# BYH_USB.net
KiCad netlist of a schematic drawn in EasyEDA Pro
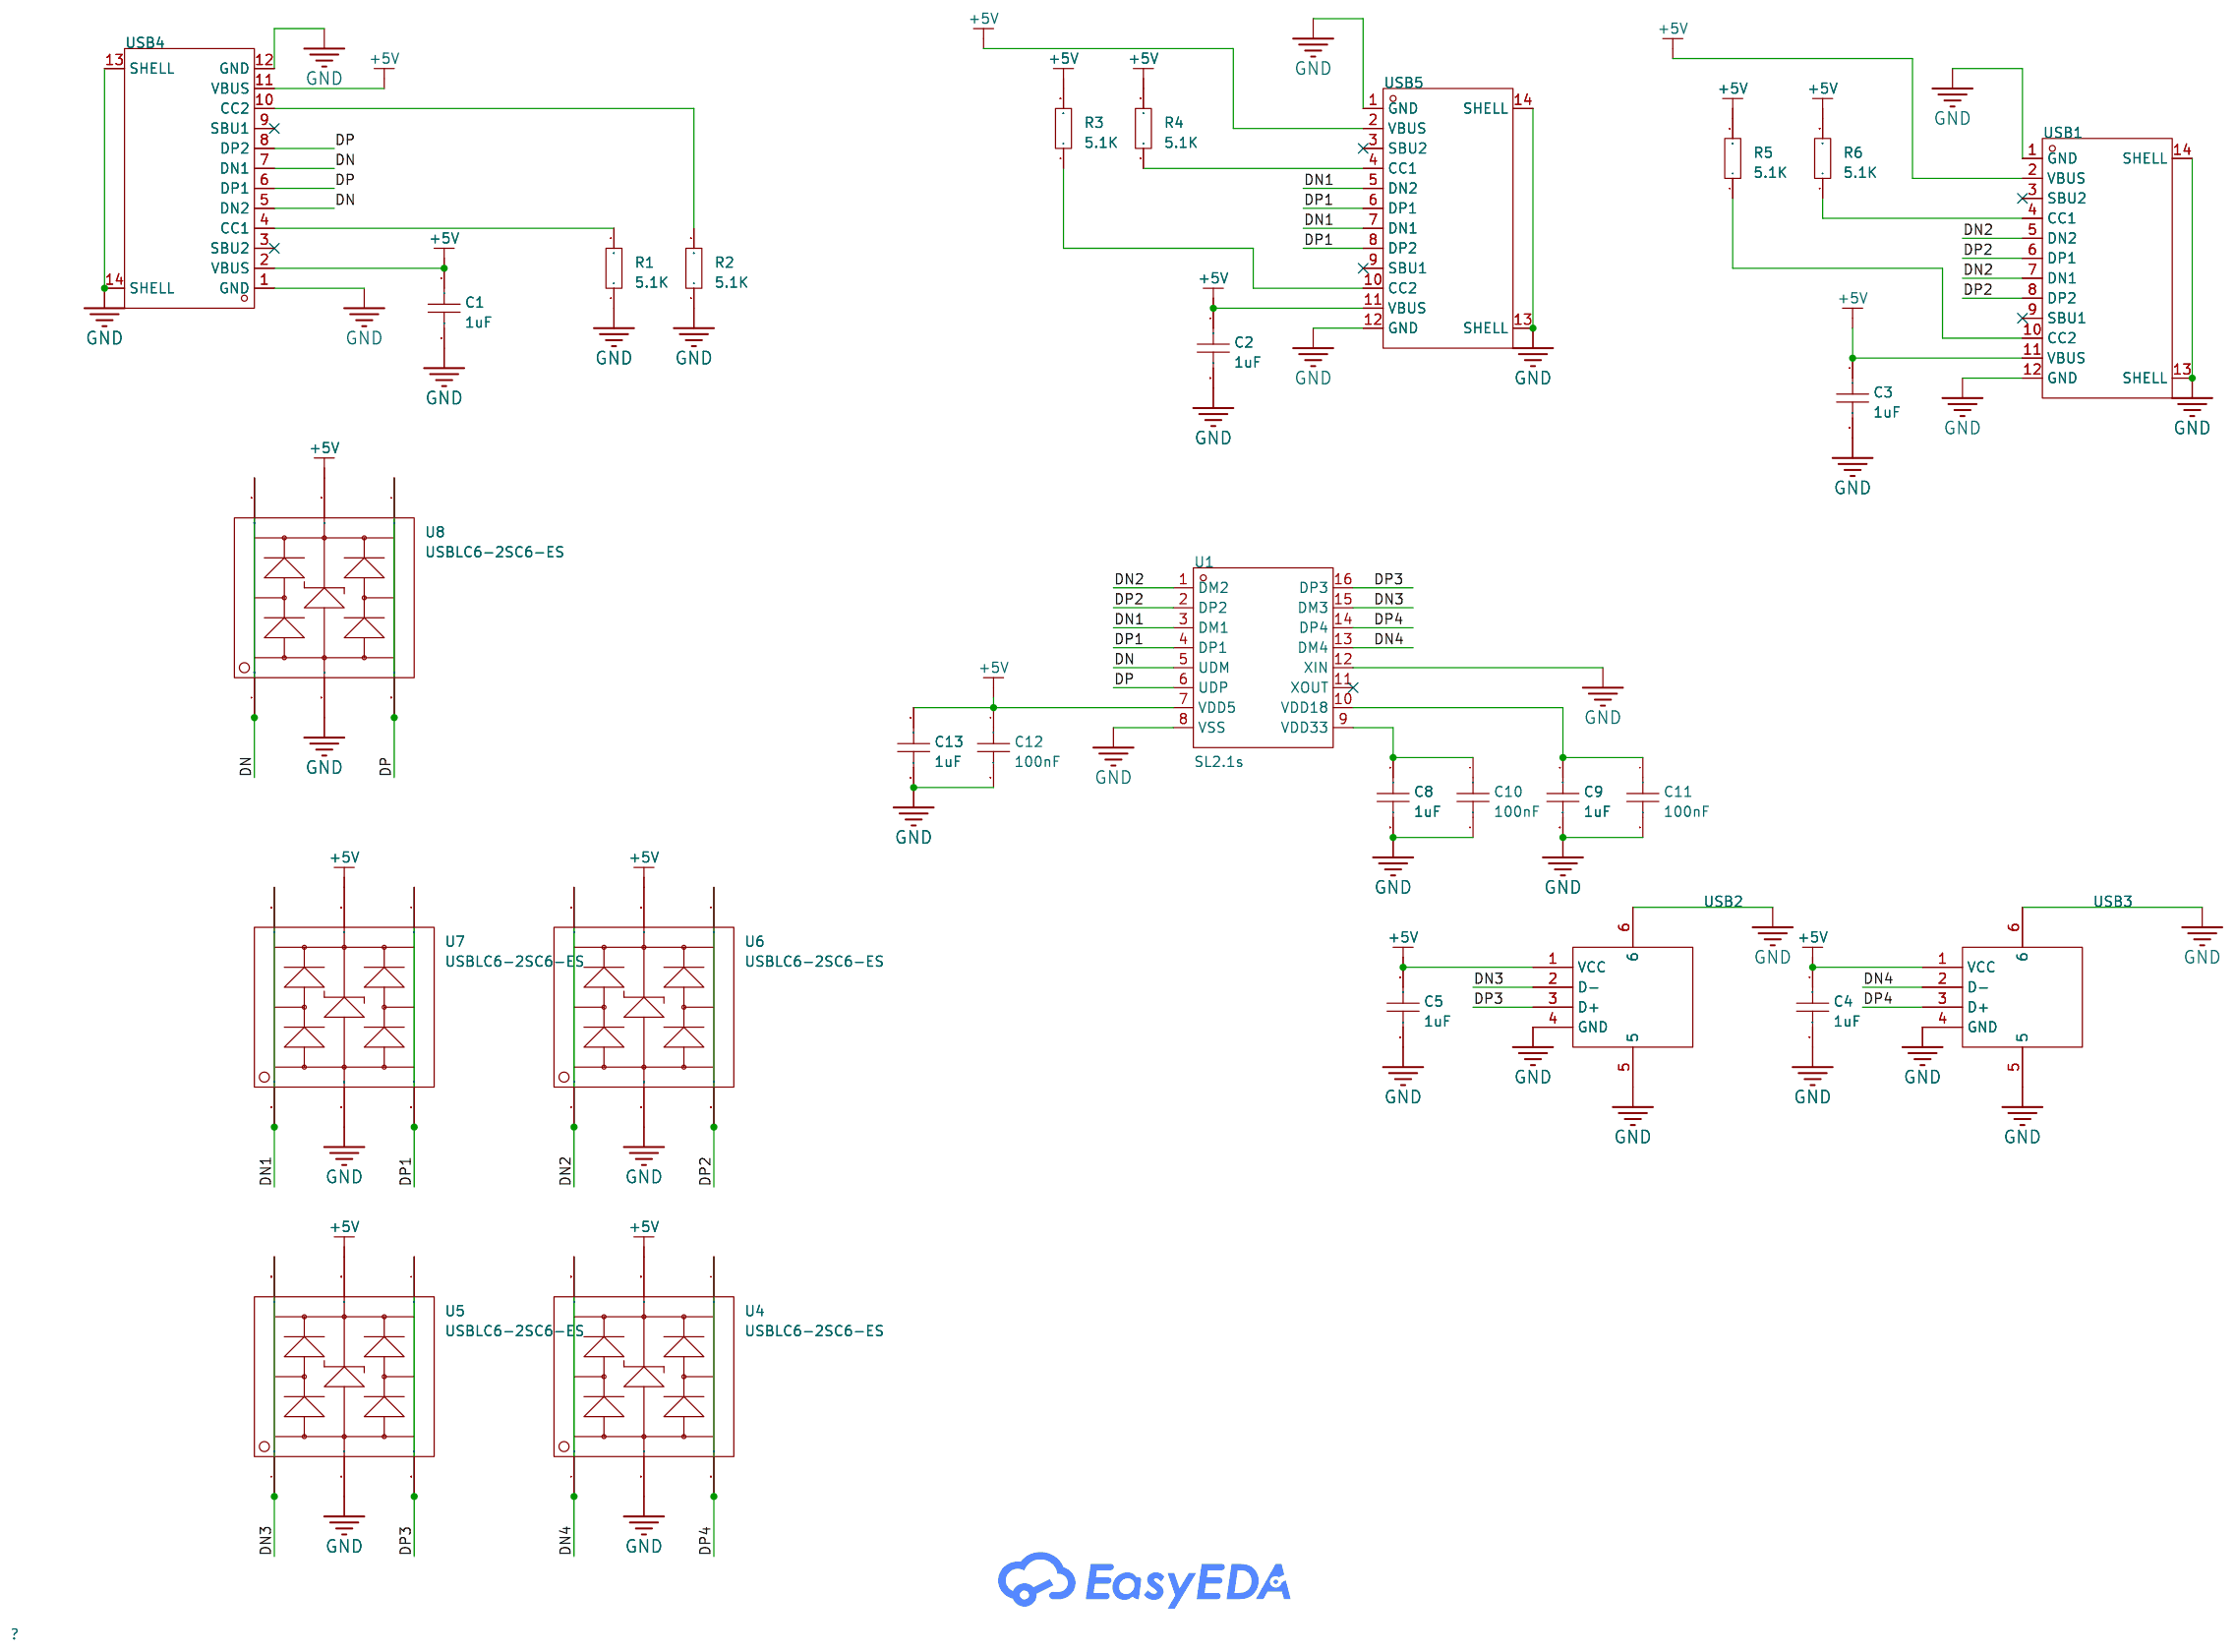
[diagram p0: schematic sheet]

(export (version "E")
  (design (tool "Eeschema 10.0.6"))
  (components
    (comp (ref "C1") (value "1uF") (footprint "easyedapro:C0603") (libsource (lib "easyedapro") (part "CAP")))
    (comp (ref "C2") (value "1uF") (footprint "easyedapro:C0603") (libsource (lib "easyedapro") (part "CAP")))
    (comp (ref "C3") (value "1uF") (footprint "easyedapro:C0603") (libsource (lib "easyedapro") (part "CAP")))
    (comp (ref "C4") (value "1uF") (footprint "easyedapro:C0603") (libsource (lib "easyedapro") (part "CAP")))
    (comp (ref "C5") (value "1uF") (footprint "easyedapro:C0603") (libsource (lib "easyedapro") (part "CAP")))
    (comp (ref "C8") (value "1uF") (footprint "easyedapro:C0603") (libsource (lib "easyedapro") (part "CAP")))
    (comp (ref "C9") (value "1uF") (footprint "easyedapro:C0603") (libsource (lib "easyedapro") (part "CAP")))
    (comp (ref "C10")
      (value "100nF")
      (footprint "easyedapro:C0603")
      (libsource (lib "easyedapro") (part "CAP"))
    )
    (comp (ref "C11")
      (value "100nF")
      (footprint "easyedapro:C0603")
      (libsource (lib "easyedapro") (part "CAP"))
    )
    (comp (ref "C12")
      (value "100nF")
      (footprint "easyedapro:C0603")
      (libsource (lib "easyedapro") (part "CAP"))
    )
    (comp (ref "C13")
      (value "1uF")
      (footprint "easyedapro:C0603")
      (libsource (lib "easyedapro") (part "CAP"))
    )
    (comp (ref "R1")
      (value "5.1K")
      (footprint "easyedapro:R0603")
      (libsource (lib "easyedapro") (part "Res"))
    )
    (comp (ref "R2")
      (value "5.1K")
      (footprint "easyedapro:R0603")
      (libsource (lib "easyedapro") (part "Res"))
    )
    (comp (ref "R3")
      (value "5.1K")
      (footprint "easyedapro:R0603")
      (libsource (lib "easyedapro") (part "Res"))
    )
    (comp (ref "R4")
      (value "5.1K")
      (footprint "easyedapro:R0603")
      (libsource (lib "easyedapro") (part "Res"))
    )
    (comp (ref "R5")
      (value "5.1K")
      (footprint "easyedapro:R0603")
      (libsource (lib "easyedapro") (part "Res"))
    )
    (comp (ref "R6")
      (value "5.1K")
      (footprint "easyedapro:R0603")
      (libsource (lib "easyedapro") (part "Res"))
    )
    (comp (ref "U1")
      (value "SL2.1s")
      (footprint "easyedapro:SSOP-16_L4.6-W2.6-P0.53-LS4.0-BL")
      (fields (field (name "Manufacturer") "CoreChips(和芯润德)"))
      (libsource (lib "easyedapro") (part "SL2.1S"))
    )
    (comp (ref "U4")
      (value "USBLC6-2SC6-ES")
      (footprint "easyedapro:SOT-23-6_L2.9-W1.6-P0.95-LS2.8-BR")
      (fields (field (name "Manufacturer") "ElecSuper(静芯)"))
      (libsource (lib "easyedapro") (part "USBLC6-2SC6-ES"))
    )
    (comp (ref "U5")
      (value "USBLC6-2SC6-ES")
      (footprint "easyedapro:SOT-23-6_L2.9-W1.6-P0.95-LS2.8-BR")
      (fields (field (name "Manufacturer") "ElecSuper(静芯)"))
      (libsource (lib "easyedapro") (part "USBLC6-2SC6-ES"))
    )
    (comp (ref "U6")
      (value "USBLC6-2SC6-ES")
      (footprint "easyedapro:SOT-23-6_L2.9-W1.6-P0.95-LS2.8-BR")
      (fields (field (name "Manufacturer") "ElecSuper(静芯)"))
      (libsource (lib "easyedapro") (part "USBLC6-2SC6-ES"))
    )
    (comp (ref "U7")
      (value "USBLC6-2SC6-ES")
      (footprint "easyedapro:SOT-23-6_L2.9-W1.6-P0.95-LS2.8-BR")
      (fields (field (name "Manufacturer") "ElecSuper(静芯)"))
      (libsource (lib "easyedapro") (part "USBLC6-2SC6-ES"))
    )
    (comp (ref "U8")
      (value "USBLC6-2SC6-ES")
      (footprint "easyedapro:SOT-23-6_L2.9-W1.6-P0.95-LS2.8-BR")
      (fields (field (name "Manufacturer") "ElecSuper(静芯)"))
      (libsource (lib "easyedapro") (part "USBLC6-2SC6-ES"))
    )
    (comp (ref "USB1")
      (value "TYPE-C 16PIN 2MD(073)")
      (footprint "easyedapro:USB-C-SMD_TYPE-C-6PIN-2MD-073")
      (fields (field (name "Manufacturer") "SHOU HAN(首韩)"))
      (libsource (lib "easyedapro") (part "TYPE-C 16PIN 2MD(073)"))
    )
    (comp (ref "USB2")
      (value "10.0 QHHTZB6.3")
      (footprint "easyedapro:USB-A-TH_10.0QHHTZB6.3")
      (fields (field (name "Manufacturer") "SHOU HAN(首韩)"))
      (libsource (lib "easyedapro") (part "10.0 QHHTZB6.3"))
    )
    (comp (ref "USB3")
      (value "10.0 QHHTZB6.3")
      (footprint "easyedapro:USB-A-TH_10.0QHHTZB6.3")
      (fields (field (name "Manufacturer") "SHOU HAN(首韩)"))
      (libsource (lib "easyedapro") (part "10.0 QHHTZB6.3"))
    )
    (comp (ref "USB4")
      (value "TYPE-C 16PIN 2MD(073)")
      (footprint "easyedapro:USB-C-SMD_TYPE-C-6PIN-2MD-073")
      (fields (field (name "Manufacturer") "SHOU HAN(首韩)"))
      (libsource (lib "easyedapro") (part "TYPE-C 16PIN 2MD(073)"))
    )
    (comp (ref "USB5")
      (value "TYPE-C 16PIN 2MD(073)")
      (footprint "easyedapro:USB-C-SMD_TYPE-C-6PIN-2MD-073")
      (fields (field (name "Manufacturer") "SHOU HAN(首韩)"))
      (libsource (lib "easyedapro") (part "TYPE-C 16PIN 2MD(073)"))
    )
  )
  (nets
    (net (code "1") (name "+5V") (class "Default")
      (node (ref "C1") (pin "1") (pinfunction "1_1") (pintype "input"))
      (node (ref "C12") (pin "1") (pinfunction "1_1") (pintype "input"))
      (node (ref "C13") (pin "1") (pinfunction "1_1") (pintype "input"))
      (node (ref "C2") (pin "1") (pinfunction "1_1") (pintype "input"))
      (node (ref "C3") (pin "1") (pinfunction "1_1") (pintype "input"))
      (node (ref "C4") (pin "1") (pinfunction "1_1") (pintype "input"))
      (node (ref "C5") (pin "1") (pinfunction "1_1") (pintype "input"))
      (node (ref "R3") (pin "2") (pinfunction "2_2") (pintype "input"))
      (node (ref "R4") (pin "2") (pinfunction "2_2") (pintype "input"))
      (node (ref "R5") (pin "2") (pinfunction "2_2") (pintype "input"))
      (node (ref "R6") (pin "2") (pinfunction "2_2") (pintype "input"))
      (node (ref "U1") (pin "7") (pinfunction "VDD5_7") (pintype "unspecified"))
      (node (ref "U4") (pin "5") (pinfunction "VCC_5") (pintype "input"))
      (node (ref "U5") (pin "5") (pinfunction "VCC_5") (pintype "input"))
      (node (ref "U6") (pin "5") (pinfunction "VCC_5") (pintype "input"))
      (node (ref "U7") (pin "5") (pinfunction "VCC_5") (pintype "input"))
      (node (ref "U8") (pin "5") (pinfunction "VCC_5") (pintype "input"))
      (node (ref "USB1") (pin "11") (pinfunction "VBUS_11") (pintype "unspecified"))
      (node (ref "USB1") (pin "2") (pinfunction "VBUS_2") (pintype "unspecified"))
      (node (ref "USB2") (pin "1") (pinfunction "VCC_1") (pintype "unspecified"))
      (node (ref "USB3") (pin "1") (pinfunction "VCC_1") (pintype "unspecified"))
      (node (ref "USB4") (pin "11") (pinfunction "VBUS_11") (pintype "unspecified"))
      (node (ref "USB4") (pin "2") (pinfunction "VBUS_2") (pintype "unspecified"))
      (node (ref "USB5") (pin "11") (pinfunction "VBUS_11") (pintype "unspecified"))
      (node (ref "USB5") (pin "2") (pinfunction "VBUS_2") (pintype "unspecified"))
    )
    (net (code "2") (name "/DN") (class "Default")
      (node (ref "U1") (pin "5") (pinfunction "UDM_5") (pintype "unspecified"))
      (node (ref "U8") (pin "1") (pinfunction "I/O1_1") (pintype "input"))
      (node (ref "U8") (pin "6") (pinfunction "I/O1_6") (pintype "input"))
      (node (ref "USB4") (pin "5") (pinfunction "DN2_5") (pintype "unspecified"))
      (node (ref "USB4") (pin "7") (pinfunction "DN1_7") (pintype "unspecified"))
    )
    (net (code "3") (name "/DN1") (class "Default")
      (node (ref "U1") (pin "3") (pinfunction "DM1_3") (pintype "unspecified"))
      (node (ref "U7") (pin "1") (pinfunction "I/O1_1") (pintype "input"))
      (node (ref "U7") (pin "6") (pinfunction "I/O1_6") (pintype "input"))
      (node (ref "USB5") (pin "5") (pinfunction "DN2_5") (pintype "unspecified"))
      (node (ref "USB5") (pin "7") (pinfunction "DN1_7") (pintype "unspecified"))
    )
    (net (code "4") (name "/DN2") (class "Default")
      (node (ref "U1") (pin "1") (pinfunction "DM2_1") (pintype "unspecified"))
      (node (ref "U6") (pin "1") (pinfunction "I/O1_1") (pintype "input"))
      (node (ref "U6") (pin "6") (pinfunction "I/O1_6") (pintype "input"))
      (node (ref "USB1") (pin "5") (pinfunction "DN2_5") (pintype "unspecified"))
      (node (ref "USB1") (pin "7") (pinfunction "DN1_7") (pintype "unspecified"))
    )
    (net (code "5") (name "/DN3") (class "Default")
      (node (ref "U1") (pin "15") (pinfunction "DM3_15") (pintype "unspecified"))
      (node (ref "U5") (pin "1") (pinfunction "I/O1_1") (pintype "input"))
      (node (ref "U5") (pin "6") (pinfunction "I/O1_6") (pintype "input"))
      (node (ref "USB2") (pin "2") (pinfunction "D-_2") (pintype "unspecified"))
    )
    (net (code "6") (name "/DN4") (class "Default")
      (node (ref "U1") (pin "13") (pinfunction "DM4_13") (pintype "unspecified"))
      (node (ref "U4") (pin "1") (pinfunction "I/O1_1") (pintype "input"))
      (node (ref "U4") (pin "6") (pinfunction "I/O1_6") (pintype "input"))
      (node (ref "USB3") (pin "2") (pinfunction "D-_2") (pintype "unspecified"))
    )
    (net (code "7") (name "/DP") (class "Default")
      (node (ref "U1") (pin "6") (pinfunction "UDP_6") (pintype "unspecified"))
      (node (ref "U8") (pin "3") (pinfunction "I/O2_3") (pintype "input"))
      (node (ref "U8") (pin "4") (pinfunction "I/O2_4") (pintype "input"))
      (node (ref "USB4") (pin "6") (pinfunction "DP1_6") (pintype "unspecified"))
      (node (ref "USB4") (pin "8") (pinfunction "DP2_8") (pintype "unspecified"))
    )
    (net (code "8") (name "/DP1") (class "Default")
      (node (ref "U1") (pin "4") (pinfunction "DP1_4") (pintype "unspecified"))
      (node (ref "U7") (pin "3") (pinfunction "I/O2_3") (pintype "input"))
      (node (ref "U7") (pin "4") (pinfunction "I/O2_4") (pintype "input"))
      (node (ref "USB5") (pin "6") (pinfunction "DP1_6") (pintype "unspecified"))
      (node (ref "USB5") (pin "8") (pinfunction "DP2_8") (pintype "unspecified"))
    )
    (net (code "9") (name "/DP2") (class "Default")
      (node (ref "U1") (pin "2") (pinfunction "DP2_2") (pintype "unspecified"))
      (node (ref "U6") (pin "3") (pinfunction "I/O2_3") (pintype "input"))
      (node (ref "U6") (pin "4") (pinfunction "I/O2_4") (pintype "input"))
      (node (ref "USB1") (pin "6") (pinfunction "DP1_6") (pintype "unspecified"))
      (node (ref "USB1") (pin "8") (pinfunction "DP2_8") (pintype "unspecified"))
    )
    (net (code "10") (name "/DP3") (class "Default")
      (node (ref "U1") (pin "16") (pinfunction "DP3_16") (pintype "unspecified"))
      (node (ref "U5") (pin "3") (pinfunction "I/O2_3") (pintype "input"))
      (node (ref "U5") (pin "4") (pinfunction "I/O2_4") (pintype "input"))
      (node (ref "USB2") (pin "3") (pinfunction "D+_3") (pintype "unspecified"))
    )
    (net (code "11") (name "/DP4") (class "Default")
      (node (ref "U1") (pin "14") (pinfunction "DP4_14") (pintype "unspecified"))
      (node (ref "U4") (pin "3") (pinfunction "I/O2_3") (pintype "input"))
      (node (ref "U4") (pin "4") (pinfunction "I/O2_4") (pintype "input"))
      (node (ref "USB3") (pin "3") (pinfunction "D+_3") (pintype "unspecified"))
    )
    (net (code "12") (name "GND") (class "Default")
      (node (ref "C1") (pin "2") (pinfunction "2_2") (pintype "input"))
      (node (ref "C10") (pin "2") (pinfunction "2_2") (pintype "input"))
      (node (ref "C11") (pin "2") (pinfunction "2_2") (pintype "input"))
      (node (ref "C12") (pin "2") (pinfunction "2_2") (pintype "input"))
      (node (ref "C13") (pin "2") (pinfunction "2_2") (pintype "input"))
      (node (ref "C2") (pin "2") (pinfunction "2_2") (pintype "input"))
      (node (ref "C3") (pin "2") (pinfunction "2_2") (pintype "input"))
      (node (ref "C4") (pin "2") (pinfunction "2_2") (pintype "input"))
      (node (ref "C5") (pin "2") (pinfunction "2_2") (pintype "input"))
      (node (ref "C8") (pin "2") (pinfunction "2_2") (pintype "input"))
      (node (ref "C9") (pin "2") (pinfunction "2_2") (pintype "input"))
      (node (ref "R1") (pin "1") (pinfunction "1_1") (pintype "input"))
      (node (ref "R2") (pin "1") (pinfunction "1_1") (pintype "input"))
      (node (ref "U1") (pin "12") (pinfunction "XIN_12") (pintype "unspecified"))
      (node (ref "U1") (pin "8") (pinfunction "VSS_8") (pintype "unspecified"))
      (node (ref "U4") (pin "2") (pinfunction "GND_2") (pintype "input"))
      (node (ref "U5") (pin "2") (pinfunction "GND_2") (pintype "input"))
      (node (ref "U6") (pin "2") (pinfunction "GND_2") (pintype "input"))
      (node (ref "U7") (pin "2") (pinfunction "GND_2") (pintype "input"))
      (node (ref "U8") (pin "2") (pinfunction "GND_2") (pintype "input"))
      (node (ref "USB1") (pin "1") (pinfunction "GND_1") (pintype "unspecified"))
      (node (ref "USB1") (pin "12") (pinfunction "GND_12") (pintype "unspecified"))
      (node (ref "USB1") (pin "13") (pinfunction "SHELL_13") (pintype "unspecified"))
      (node (ref "USB1") (pin "14") (pinfunction "SHELL_14") (pintype "unspecified"))
      (node (ref "USB2") (pin "4") (pinfunction "GND_4") (pintype "unspecified"))
      (node (ref "USB2") (pin "5") (pinfunction "5_5") (pintype "unspecified"))
      (node (ref "USB2") (pin "6") (pinfunction "6_6") (pintype "unspecified"))
      (node (ref "USB3") (pin "4") (pinfunction "GND_4") (pintype "unspecified"))
      (node (ref "USB3") (pin "5") (pinfunction "5_5") (pintype "unspecified"))
      (node (ref "USB3") (pin "6") (pinfunction "6_6") (pintype "unspecified"))
      (node (ref "USB4") (pin "1") (pinfunction "GND_1") (pintype "unspecified"))
      (node (ref "USB4") (pin "12") (pinfunction "GND_12") (pintype "unspecified"))
      (node (ref "USB4") (pin "13") (pinfunction "SHELL_13") (pintype "unspecified"))
      (node (ref "USB4") (pin "14") (pinfunction "SHELL_14") (pintype "unspecified"))
      (node (ref "USB5") (pin "1") (pinfunction "GND_1") (pintype "unspecified"))
      (node (ref "USB5") (pin "12") (pinfunction "GND_12") (pintype "unspecified"))
      (node (ref "USB5") (pin "13") (pinfunction "SHELL_13") (pintype "unspecified"))
      (node (ref "USB5") (pin "14") (pinfunction "SHELL_14") (pintype "unspecified"))
    )
    (net (code "13") (name "Net-(U1-VDD18)") (class "Default")
      (node (ref "C11") (pin "1") (pinfunction "1_1") (pintype "input"))
      (node (ref "C9") (pin "1") (pinfunction "1_1") (pintype "input"))
      (node (ref "U1") (pin "10") (pinfunction "VDD18_10") (pintype "unspecified"))
    )
    (net (code "14") (name "Net-(U1-VDD33)") (class "Default")
      (node (ref "C10") (pin "1") (pinfunction "1_1") (pintype "input"))
      (node (ref "C8") (pin "1") (pinfunction "1_1") (pintype "input"))
      (node (ref "U1") (pin "9") (pinfunction "VDD33_9") (pintype "unspecified"))
    )
    (net (code "15") (name "Net-(USB1-CC1)") (class "Default")
      (node (ref "R6") (pin "1") (pinfunction "1_1") (pintype "input"))
      (node (ref "USB1") (pin "4") (pinfunction "CC1_4") (pintype "unspecified"))
    )
    (net (code "16") (name "Net-(USB1-CC2)") (class "Default")
      (node (ref "R5") (pin "1") (pinfunction "1_1") (pintype "input"))
      (node (ref "USB1") (pin "10") (pinfunction "CC2_10") (pintype "unspecified"))
    )
    (net (code "17") (name "Net-(USB4-CC1)") (class "Default")
      (node (ref "R1") (pin "2") (pinfunction "2_2") (pintype "input"))
      (node (ref "USB4") (pin "4") (pinfunction "CC1_4") (pintype "unspecified"))
    )
    (net (code "18") (name "Net-(USB4-CC2)") (class "Default")
      (node (ref "R2") (pin "2") (pinfunction "2_2") (pintype "input"))
      (node (ref "USB4") (pin "10") (pinfunction "CC2_10") (pintype "unspecified"))
    )
    (net (code "19") (name "Net-(USB5-CC1)") (class "Default")
      (node (ref "R4") (pin "1") (pinfunction "1_1") (pintype "input"))
      (node (ref "USB5") (pin "4") (pinfunction "CC1_4") (pintype "unspecified"))
    )
    (net (code "20") (name "Net-(USB5-CC2)") (class "Default")
      (node (ref "R3") (pin "1") (pinfunction "1_1") (pintype "input"))
      (node (ref "USB5") (pin "10") (pinfunction "CC2_10") (pintype "unspecified"))
    )
    (net (code "21") (name "unconnected-(U1-XOUT-Pad11)") (class "Default")
      (node (ref "U1") (pin "11") (pinfunction "XOUT_11") (pintype "unspecified+no_connect"))
    )
    (net (code "22") (name "unconnected-(USB1-SBU1-Pad9)") (class "Default")
      (node (ref "USB1") (pin "9") (pinfunction "SBU1_9") (pintype "unspecified+no_connect"))
    )
    (net (code "23") (name "unconnected-(USB1-SBU2-Pad3)") (class "Default")
      (node (ref "USB1") (pin "3") (pinfunction "SBU2_3") (pintype "unspecified+no_connect"))
    )
    (net (code "24") (name "unconnected-(USB4-SBU1-Pad9)") (class "Default")
      (node (ref "USB4") (pin "9") (pinfunction "SBU1_9") (pintype "unspecified+no_connect"))
    )
    (net (code "25") (name "unconnected-(USB4-SBU2-Pad3)") (class "Default")
      (node (ref "USB4") (pin "3") (pinfunction "SBU2_3") (pintype "unspecified+no_connect"))
    )
    (net (code "26") (name "unconnected-(USB5-SBU1-Pad9)") (class "Default")
      (node (ref "USB5") (pin "9") (pinfunction "SBU1_9") (pintype "unspecified+no_connect"))
    )
    (net (code "27") (name "unconnected-(USB5-SBU2-Pad3)") (class "Default")
      (node (ref "USB5") (pin "3") (pinfunction "SBU2_3") (pintype "unspecified+no_connect"))
    )
  )
)
